# RailSlave.net
KiCad netlist of a schematic drawn in EAGLE
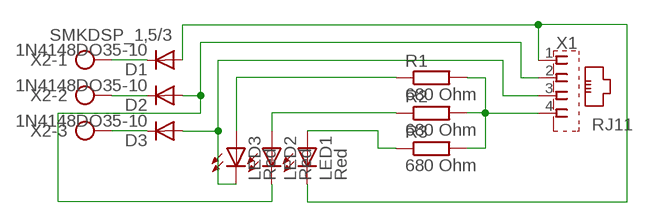
[diagram p0: schematic, sheet 1]

(export (version "E")
  (design (tool "Eeschema 10.0.6"))
  (components
    (comp (ref "D1")
      (value "1N4148DO35-10")
      (footprint "eagle-import:DO35-10")
      (libsource (lib "eagle-import") (part "1N4148DO35-10"))
    )
    (comp (ref "D2")
      (value "1N4148DO35-10")
      (footprint "eagle-import:DO35-10")
      (libsource (lib "eagle-import") (part "1N4148DO35-10"))
    )
    (comp (ref "D3")
      (value "1N4148DO35-10")
      (footprint "eagle-import:DO35-10")
      (libsource (lib "eagle-import") (part "1N4148DO35-10"))
    )
    (comp (ref "LED1")
      (value "Red")
      (footprint "eagle-import:LED3MM")
      (libsource (lib "eagle-import") (part "LED3MM"))
    )
    (comp (ref "LED2")
      (value "Red")
      (footprint "eagle-import:LED3MM")
      (libsource (lib "eagle-import") (part "LED3MM"))
    )
    (comp (ref "LED3")
      (value "Red")
      (footprint "eagle-import:LED3MM")
      (libsource (lib "eagle-import") (part "LED3MM"))
    )
    (comp (ref "R1")
      (value "680 Ohm")
      (footprint "eagle-import:0207_10")
      (libsource (lib "eagle-import") (part "R-EU_0207/10"))
    )
    (comp (ref "R2")
      (value "680 Ohm")
      (footprint "eagle-import:0207_10")
      (libsource (lib "eagle-import") (part "R-EU_0207/10"))
    )
    (comp (ref "R3")
      (value "680 Ohm")
      (footprint "eagle-import:0207_10")
      (libsource (lib "eagle-import") (part "R-EU_0207/10"))
    )
    (comp (ref "X1")
      (value "RJ11")
      (footprint "eagle-import:RJ116PC4")
      (libsource (lib "eagle-import") (part "RJ11-6PC4"))
    )
    (comp (ref "X2")
      (value "SMKDSP_1,5/3")
      (footprint "eagle-import:SMKDSP_1,5_3")
      (fields (field (name "MF") "FARNELL") (field (name "MPN") "1733583"))
      (libsource (lib "eagle-import") (part "SMKDSP_1,5/3"))
    )
  )
  (nets
    (net (code "1") (name "Net-(LED1-C)") (class "Default")
      (node (ref "D1") (pin "A") (pinfunction "A_A") (pintype "passive"))
      (node (ref "LED1") (pin "K") (pinfunction "C_K") (pintype "passive"))
      (node (ref "X1") (pin "1") (pinfunction "1_1") (pintype "passive"))
    )
    (net (code "2") (name "Net-(LED1-PadA)") (class "Default")
      (node (ref "LED1") (pin "A") (pinfunction "A_A") (pintype "passive"))
      (node (ref "R3") (pin "1") (pinfunction "1_1") (pintype "passive"))
    )
    (net (code "3") (name "Net-(LED2-C)") (class "Default")
      (node (ref "D2") (pin "A") (pinfunction "A_A") (pintype "passive"))
      (node (ref "LED2") (pin "K") (pinfunction "C_K") (pintype "passive"))
      (node (ref "X1") (pin "2") (pinfunction "2_2") (pintype "passive"))
    )
    (net (code "4") (name "Net-(LED2-PadA)") (class "Default")
      (node (ref "LED2") (pin "A") (pinfunction "A_A") (pintype "passive"))
      (node (ref "R2") (pin "1") (pinfunction "1_1") (pintype "passive"))
    )
    (net (code "5") (name "Net-(LED3-C)") (class "Default")
      (node (ref "D3") (pin "A") (pinfunction "A_A") (pintype "passive"))
      (node (ref "LED3") (pin "K") (pinfunction "C_K") (pintype "passive"))
      (node (ref "X1") (pin "3") (pinfunction "3_3") (pintype "passive"))
    )
    (net (code "6") (name "Net-(LED3-PadA)") (class "Default")
      (node (ref "LED3") (pin "A") (pinfunction "A_A") (pintype "passive"))
      (node (ref "R1") (pin "1") (pinfunction "1_1") (pintype "passive"))
    )
    (net (code "7") (name "Net-(R1-Pad2)") (class "Default")
      (node (ref "R1") (pin "2") (pinfunction "2_2") (pintype "passive"))
      (node (ref "R2") (pin "2") (pinfunction "2_2") (pintype "passive"))
      (node (ref "R3") (pin "2") (pinfunction "2_2") (pintype "passive"))
      (node (ref "X1") (pin "4") (pinfunction "4_4") (pintype "passive"))
    )
    (net (code "8") (name "Net-(X2A-KL)") (class "Default")
      (node (ref "D1") (pin "C") (pinfunction "C_C") (pintype "passive"))
      (node (ref "X2") (pin "1") (pinfunction "KL_1") (pintype "passive"))
    )
    (net (code "9") (name "Net-(X2B-KL)") (class "Default")
      (node (ref "D2") (pin "C") (pinfunction "C_C") (pintype "passive"))
      (node (ref "X2") (pin "2") (pinfunction "KL_2") (pintype "passive"))
    )
    (net (code "10") (name "Net-(X2C-KL)") (class "Default")
      (node (ref "D3") (pin "C") (pinfunction "C_C") (pintype "passive"))
      (node (ref "X2") (pin "3") (pinfunction "KL_3") (pintype "passive"))
    )
  )
)
